# rc_gen.net
KiCad netlist of a schematic drawn in Altium Designer
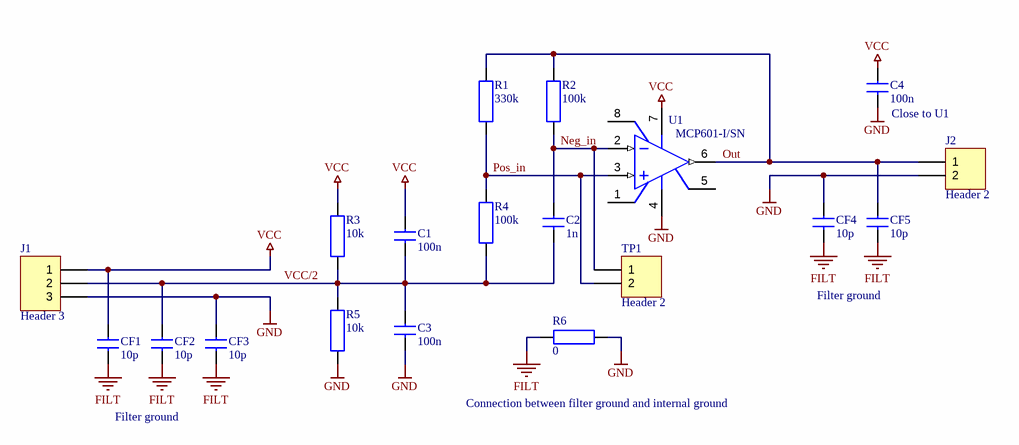
[diagram p0: rc_gen.SchDoc]

(export (version "E")
  (design (tool "Eeschema 10.0.6"))
  (components
    (comp (ref "C1")
      (value "100n")
      (footprint "0805")
      (description "Normaler Kondensator")
      (libsource (lib "DEVICE_HSLU") (part "C?"))
    )
    (comp (ref "C2")
      (value "1n")
      (footprint "0805")
      (description "Normaler Kondensator")
      (libsource (lib "DEVICE_HSLU") (part "C?"))
    )
    (comp (ref "C3")
      (value "100n")
      (footprint "0805")
      (description "Normaler Kondensator")
      (libsource (lib "DEVICE_HSLU") (part "C?"))
    )
    (comp (ref "C4")
      (value "100n")
      (footprint "0805")
      (description "Normaler Kondensator")
      (libsource (lib "DEVICE_HSLU") (part "C?"))
    )
    (comp (ref "CF1")
      (value "10p")
      (footprint "0805")
      (description "Normaler Kondensator")
      (libsource (lib "DEVICE_HSLU") (part "C?"))
    )
    (comp (ref "CF2")
      (value "10p")
      (footprint "0805")
      (description "Normaler Kondensator")
      (libsource (lib "DEVICE_HSLU") (part "C?"))
    )
    (comp (ref "CF3")
      (value "10p")
      (footprint "0805")
      (description "Normaler Kondensator")
      (libsource (lib "DEVICE_HSLU") (part "C?"))
    )
    (comp (ref "CF4")
      (value "10p")
      (footprint "0805")
      (description "Normaler Kondensator")
      (libsource (lib "DEVICE_HSLU") (part "C?"))
    )
    (comp (ref "CF5")
      (value "10p")
      (footprint "0805")
      (description "Normaler Kondensator")
      (libsource (lib "DEVICE_HSLU") (part "C?"))
    )
    (comp (ref "J1")
      (value "Header 3")
      (footprint "HDR1X3")
      (description "Header, 3-Pin")
      (fields (field (name "PUBLISHER") "Altium Limited"))
      (libsource (lib "Miscellaneous Connectors") (part "Header 3"))
    )
    (comp (ref "J2")
      (value "Header 2")
      (footprint "HDR1X2")
      (description "Header, 2-Pin")
      (fields (field (name "PUBLISHER") "Altium Limited"))
      (libsource (lib "Miscellaneous Connectors") (part "Header 2"))
    )
    (comp (ref "R1")
      (value "330k")
      (footprint "0805")
      (description "Normaler Widerstand")
      (libsource (lib "DEVICE_HSLU") (part "R?"))
    )
    (comp (ref "R2")
      (value "100k")
      (footprint "0805")
      (description "Normaler Widerstand")
      (libsource (lib "DEVICE_HSLU") (part "R?"))
    )
    (comp (ref "R3")
      (value "10k")
      (footprint "0805")
      (description "Normaler Widerstand")
      (libsource (lib "DEVICE_HSLU") (part "R?"))
    )
    (comp (ref "R4")
      (value "100k")
      (footprint "0805")
      (description "Normaler Widerstand")
      (libsource (lib "DEVICE_HSLU") (part "R?"))
    )
    (comp (ref "R5")
      (value "10k")
      (footprint "0805")
      (description "Normaler Widerstand")
      (libsource (lib "DEVICE_HSLU") (part "R?"))
    )
    (comp (ref "R6")
      (value "0")
      (footprint "0805")
      (description "Normaler Widerstand")
      (libsource (lib "DEVICE_HSLU") (part "R?"))
    )
    (comp (ref "TP1")
      (value "Header 2")
      (footprint "HDR1X2")
      (description "Header, 2-Pin")
      (fields (field (name "PUBLISHER") "Altium Limited"))
      (libsource (lib "Miscellaneous Connectors") (part "Header 2"))
    )
    (comp (ref "U1")
      (value "MCP601-I/SN")
      (footprint "SOIC-SN8_N")
      (description "2.7V to 6.0V Single Supply CMOS Operational Amplifier, 8-Pin SOIC, Industrial Temperature")
      (fields (field (name "PUBLISHER") "Altium Limited"))
      (libsource (lib "Microchip Linear Devices") (part "MCP601-I/SN"))
    )
  )
  (nets
    (net (code "1") (name "/Neg_in") (class "Default")
      (node (ref "C2") (pin "1") (pinfunction "1_1") (pintype "passive"))
      (node (ref "R2") (pin "1") (pintype "passive"))
      (node (ref "TP1") (pin "1") (pinfunction "1_1") (pintype "passive"))
      (node (ref "U1") (pin "2") (pinfunction "VIN-_2") (pintype "input"))
    )
    (net (code "2") (name "/Out") (class "Default")
      (node (ref "CF5") (pin "1") (pinfunction "1_1") (pintype "passive"))
      (node (ref "J2") (pin "1") (pinfunction "1_1") (pintype "passive"))
      (node (ref "R1") (pin "2") (pintype "passive"))
      (node (ref "R2") (pin "2") (pintype "passive"))
      (node (ref "U1") (pin "6") (pinfunction "VOUT_6") (pintype "output"))
    )
    (net (code "3") (name "/Pos_in") (class "Default")
      (node (ref "R1") (pin "1") (pintype "passive"))
      (node (ref "R4") (pin "2") (pintype "passive"))
      (node (ref "TP1") (pin "2") (pinfunction "2_2") (pintype "passive"))
      (node (ref "U1") (pin "3") (pinfunction "VIN+_3") (pintype "input"))
    )
    (net (code "4") (name "/VCC{slash}2") (class "Default")
      (node (ref "C1") (pin "2") (pinfunction "2_2") (pintype "passive"))
      (node (ref "C2") (pin "2") (pinfunction "2_2") (pintype "passive"))
      (node (ref "C3") (pin "1") (pinfunction "1_1") (pintype "passive"))
      (node (ref "CF2") (pin "1") (pinfunction "1_1") (pintype "passive"))
      (node (ref "J1") (pin "2") (pinfunction "2_2") (pintype "passive"))
      (node (ref "R3") (pin "1") (pintype "passive"))
      (node (ref "R4") (pin "1") (pintype "passive"))
      (node (ref "R5") (pin "2") (pintype "passive"))
    )
    (net (code "5") (name "FILT") (class "Default")
      (node (ref "CF1") (pin "2") (pinfunction "2_2") (pintype "passive"))
      (node (ref "CF2") (pin "2") (pinfunction "2_2") (pintype "passive"))
      (node (ref "CF3") (pin "2") (pinfunction "2_2") (pintype "passive"))
      (node (ref "CF4") (pin "2") (pinfunction "2_2") (pintype "passive"))
      (node (ref "CF5") (pin "2") (pinfunction "2_2") (pintype "passive"))
      (node (ref "R6") (pin "1") (pintype "passive"))
    )
    (net (code "6") (name "GND") (class "Default")
      (node (ref "C3") (pin "2") (pinfunction "2_2") (pintype "passive"))
      (node (ref "C4") (pin "2") (pinfunction "2_2") (pintype "passive"))
      (node (ref "CF3") (pin "1") (pinfunction "1_1") (pintype "passive"))
      (node (ref "CF4") (pin "1") (pinfunction "1_1") (pintype "passive"))
      (node (ref "J1") (pin "3") (pinfunction "3_3") (pintype "passive"))
      (node (ref "J2") (pin "2") (pinfunction "2_2") (pintype "passive"))
      (node (ref "R5") (pin "1") (pintype "passive"))
      (node (ref "R6") (pin "2") (pintype "passive"))
      (node (ref "U1") (pin "4") (pinfunction "VSS_4") (pintype "power_in"))
    )
    (net (code "7") (name "VCC") (class "Default")
      (node (ref "C1") (pin "1") (pinfunction "1_1") (pintype "passive"))
      (node (ref "C4") (pin "1") (pinfunction "1_1") (pintype "passive"))
      (node (ref "CF1") (pin "1") (pinfunction "1_1") (pintype "passive"))
      (node (ref "J1") (pin "1") (pinfunction "1_1") (pintype "passive"))
      (node (ref "R3") (pin "2") (pintype "passive"))
      (node (ref "U1") (pin "7") (pinfunction "VDD_7") (pintype "power_in"))
    )
    (net (code "8") (name "unconnected-(U1-NC-Pad1)") (class "Default")
      (node (ref "U1") (pin "1") (pinfunction "NC_1") (pintype "passive"))
    )
    (net (code "9") (name "unconnected-(U1-NC-Pad5)") (class "Default")
      (node (ref "U1") (pin "5") (pinfunction "NC_5") (pintype "passive"))
    )
    (net (code "10") (name "unconnected-(U1-NC-Pad8)") (class "Default")
      (node (ref "U1") (pin "8") (pinfunction "NC_8") (pintype "passive"))
    )
  )
)
